# Comparator_Breakout_TLV3501.net
KiCad netlist of a schematic drawn in EAGLE
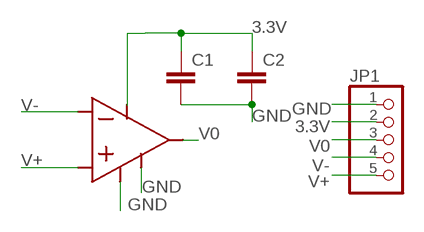
[diagram p0: schematic, sheet 1]

(export (version "E")
  (design (tool "Eeschema 10.0.6"))
  (components
    (comp (ref "C1")
      (value "C-EUC0805")
      (footprint "eagle-import:C0805")
      (libsource (lib "eagle-import") (part "C-EUC0805"))
    )
    (comp (ref "C2")
      (value "C-EUC0805")
      (footprint "eagle-import:C0805")
      (libsource (lib "eagle-import") (part "C-EUC0805"))
    )
    (comp (ref "JP1")
      (value "PINHD-1X5")
      (footprint "eagle-import:1X05")
      (libsource (lib "eagle-import") (part "PINHD-1X5"))
    )
    (comp (ref "U$1")
      (value "TLV3501")
      (footprint "eagle-import:SOT23-6")
      (libsource (lib "eagle-import") (part "TLV3501"))
    )
  )
  (nets
    (net (code "1") (name "/3.3V") (class "Default")
      (node (ref "C1") (pin "1") (pinfunction "1_1") (pintype "passive"))
      (node (ref "C2") (pin "1") (pinfunction "1_1") (pintype "passive"))
      (node (ref "JP1") (pin "2") (pinfunction "2_2") (pintype "passive"))
      (node (ref "U$1") (pin "P$4") (pinfunction "V+_P$4") (pintype "bidirectional"))
    )
    (net (code "2") (name "/GND") (class "Default")
      (node (ref "C1") (pin "2") (pinfunction "2_2") (pintype "passive"))
      (node (ref "C2") (pin "2") (pinfunction "2_2") (pintype "passive"))
      (node (ref "JP1") (pin "1") (pinfunction "1_1") (pintype "passive"))
      (node (ref "U$1") (pin "P$2") (pinfunction "V-_P$2") (pintype "bidirectional"))
      (node (ref "U$1") (pin "P$6") (pinfunction "SHDN_P$6") (pintype "bidirectional"))
    )
    (net (code "3") (name "/V+") (class "Default")
      (node (ref "JP1") (pin "5") (pinfunction "5_5") (pintype "passive"))
      (node (ref "U$1") (pin "P$3") (pinfunction "IN+_P$3") (pintype "bidirectional"))
    )
    (net (code "4") (name "/V-") (class "Default")
      (node (ref "JP1") (pin "4") (pinfunction "4_4") (pintype "passive"))
      (node (ref "U$1") (pin "P$1") (pinfunction "IN-_P$1") (pintype "bidirectional"))
    )
    (net (code "5") (name "/V0") (class "Default")
      (node (ref "JP1") (pin "3") (pinfunction "3_3") (pintype "passive"))
      (node (ref "U$1") (pin "P$5") (pinfunction "OUT_P$5") (pintype "bidirectional"))
    )
  )
)
